# airwatch.net
KiCad netlist of a schematic drawn in EAGLE
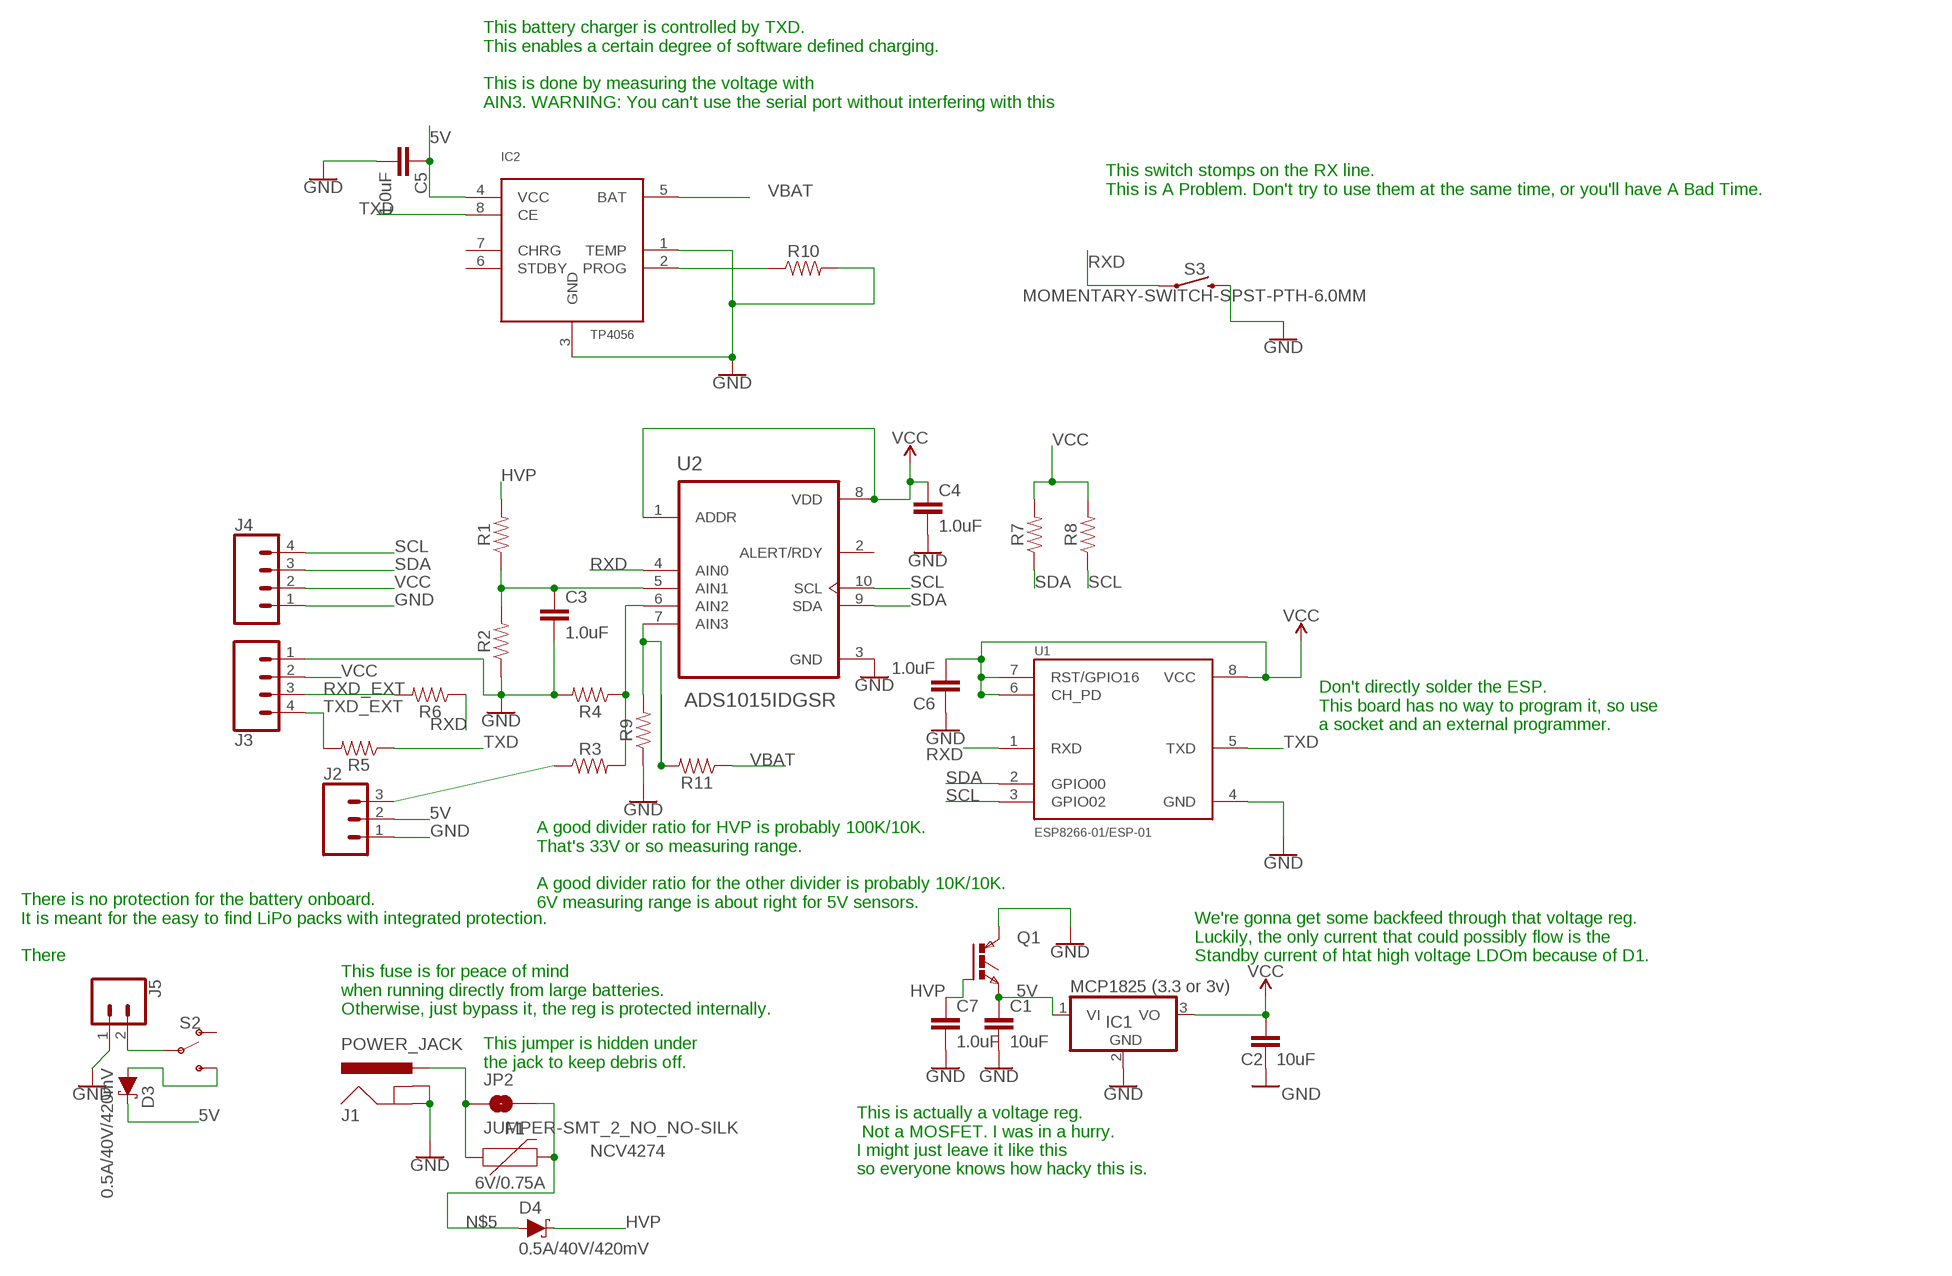
[diagram p0: schematic, sheet 1]

(export (version "E")
  (design (tool "Eeschema 10.0.6"))
  (components
    (comp (ref "C1")
      (value "10uF")
      (footprint "eagle-import:0805")
      (libsource (lib "eagle-import") (part "10UF-0805-10V-10%"))
    )
    (comp (ref "C2")
      (value "10uF")
      (footprint "eagle-import:0805")
      (libsource (lib "eagle-import") (part "10UF-0805-10V-10%"))
    )
    (comp (ref "C3")
      (value "1.0uF")
      (footprint "eagle-import:0805-EZ")
      (libsource (lib "eagle-import") (part "1.0UF-0805-25V-10%"))
    )
    (comp (ref "C4")
      (value "1.0uF")
      (footprint "eagle-import:0805-EZ")
      (libsource (lib "eagle-import") (part "1.0UF-0805-25V-10%"))
    )
    (comp (ref "C5")
      (value "1.0uF")
      (footprint "eagle-import:0805-EZ")
      (libsource (lib "eagle-import") (part "1.0UF-0805-25V-10%"))
    )
    (comp (ref "C6")
      (value "1.0uF")
      (footprint "eagle-import:1206-EZ")
      (libsource (lib "eagle-import") (part "1.0UF-1206-50V-10%"))
    )
    (comp (ref "C7")
      (value "1.0uF")
      (footprint "eagle-import:0805-EZ")
      (libsource (lib "eagle-import") (part "1.0UF-0805-25V-10%"))
    )
    (comp (ref "D3")
      (value "0.5A/40V/420mV")
      (footprint "eagle-import:SOD-323")
      (libsource (lib "eagle-import") (part "DIODE-SCHOTTKY-PMEG4005EJ"))
    )
    (comp (ref "D4")
      (value "0.5A/40V/420mV")
      (footprint "eagle-import:SOD-323")
      (libsource (lib "eagle-import") (part "DIODE-SCHOTTKY-PMEG4005EJ"))
    )
    (comp (ref "F1")
      (value "6V/0.75A")
      (footprint "eagle-import:1206")
      (libsource (lib "eagle-import") (part "PPTC_THREE-QUARTER-AMP"))
    )
    (comp (ref "IC1")
      (value "MCP1825 (3.3 or 3v)")
      (footprint "eagle-import:SOT223")
      (libsource (lib "eagle-import") (part "MCP1703DB"))
    )
    (comp (ref "IC2")
      (value "TP4056")
      (footprint "eagle-import:SOP-8")
      (fields (field (name "MF") "NanJing Top Power ASIC Corp.") (field (name "MP") "TP4056 "))
      (libsource (lib "eagle-import") (part "TP4056"))
    )
    (comp (ref "J1")
      (value "POWER_JACK")
      (footprint "eagle-import:POWER_JACK_PTH")
      (libsource (lib "eagle-import") (part "POWER_JACK"))
    )
    (comp (ref "J2")
      (value "CONN_03JST-PTH-VERT")
      (footprint "eagle-import:JST-3-PTH-VERT")
      (libsource (lib "eagle-import") (part "CONN_03JST-PTH-VERT"))
    )
    (comp (ref "J3")
      (value "CONN_04JST-PTH-VERT")
      (footprint "eagle-import:JST-4-PTH-VERT")
      (libsource (lib "eagle-import") (part "CONN_04JST-PTH-VERT"))
    )
    (comp (ref "J4")
      (value "CONN_04JST-PTH-VERT")
      (footprint "eagle-import:JST-4-PTH-VERT")
      (libsource (lib "eagle-import") (part "CONN_04JST-PTH-VERT"))
    )
    (comp (ref "J5")
      (value "CONN_02JST-PTH-2")
      (footprint "eagle-import:JST-2-PTH")
      (libsource (lib "eagle-import") (part "CONN_02JST-PTH-2"))
    )
    (comp (ref "JP2")
      (value "JUMPER-SMT_2_NO_NO-SILK")
      (footprint "eagle-import:SMT-JUMPER_2_NO_NO-SILK")
      (libsource (lib "eagle-import") (part "JUMPER-SMT_2_NO_NO-SILK"))
    )
    (comp (ref "Q1")
      (value "NCV4274")
      (footprint "eagle-import:TO252_STM")
      (libsource (lib "eagle-import") (part "IGBTTO252_STM"))
    )
    (comp (ref "R1")
      (value "RESISTOR0805")
      (footprint "eagle-import:0805-EZ")
      (libsource (lib "eagle-import") (part "RESISTOR0805"))
    )
    (comp (ref "R2")
      (value "RESISTOR0805")
      (footprint "eagle-import:0805-EZ")
      (libsource (lib "eagle-import") (part "RESISTOR0805"))
    )
    (comp (ref "R3")
      (value "RESISTOR0805")
      (footprint "eagle-import:0805-EZ")
      (libsource (lib "eagle-import") (part "RESISTOR0805"))
    )
    (comp (ref "R4")
      (value "RESISTOR0805")
      (footprint "eagle-import:0805-EZ")
      (libsource (lib "eagle-import") (part "RESISTOR0805"))
    )
    (comp (ref "R5")
      (value "RESISTOR0805")
      (footprint "eagle-import:0805-EZ")
      (libsource (lib "eagle-import") (part "RESISTOR0805"))
    )
    (comp (ref "R6")
      (value "RESISTOR0805")
      (footprint "eagle-import:0805-EZ")
      (libsource (lib "eagle-import") (part "RESISTOR0805"))
    )
    (comp (ref "R7")
      (value "RESISTOR0805")
      (footprint "eagle-import:0805-EZ")
      (libsource (lib "eagle-import") (part "RESISTOR0805"))
    )
    (comp (ref "R8")
      (value "RESISTOR0805")
      (footprint "eagle-import:0805-EZ")
      (libsource (lib "eagle-import") (part "RESISTOR0805"))
    )
    (comp (ref "R9")
      (value "RESISTOR0805")
      (footprint "eagle-import:0805-EZ")
      (libsource (lib "eagle-import") (part "RESISTOR0805"))
    )
    (comp (ref "R10")
      (value "RESISTOR0805")
      (footprint "eagle-import:0805-EZ")
      (libsource (lib "eagle-import") (part "RESISTOR0805"))
    )
    (comp (ref "R11")
      (value "RESISTOR0805")
      (footprint "eagle-import:0805-EZ")
      (libsource (lib "eagle-import") (part "RESISTOR0805"))
    )
    (comp (ref "S2")
      (value "SWITCH-SPDT-PTH-11.6X4.0MM-LOCK")
      (footprint "eagle-import:SWITCH_SPDT_PTH_11.6X4.0MM_LOCK")
      (libsource (lib "eagle-import") (part "SWITCH-SPDT-PTH-11.6X4.0MM-LOCK"))
    )
    (comp (ref "S3")
      (value "MOMENTARY-SWITCH-SPST-PTH-6.0MM")
      (footprint "eagle-import:TACTILE_SWITCH_PTH_6.0MM")
      (libsource (lib "eagle-import") (part "MOMENTARY-SWITCH-SPST-PTH-6.0MM"))
    )
    (comp (ref "U1")
      (value "ESP8266-01/ESP-01")
      (footprint "eagle-import:XCVR_ESP8266-01_ESP-01")
      (fields (field (name "MF") "AI-Thinker"))
      (libsource (lib "eagle-import") (part "ESP8266-01/ESP-01"))
    )
    (comp (ref "U2")
      (value "ADS1015IDGSR")
      (footprint "eagle-import:SOP50P490X110-10N")
      (fields (field (name "MF") "Texas Instruments"))
      (libsource (lib "eagle-import") (part "ADS1015IDGSR"))
    )
  )
  (nets
    (net (code "1") (name "/5V") (class "Default")
      (node (ref "C1") (pin "1") (pinfunction "1_1") (pintype "passive"))
      (node (ref "C5") (pin "1") (pinfunction "1_1") (pintype "passive"))
      (node (ref "D3") (pin "C") (pinfunction "C_C") (pintype "passive"))
      (node (ref "IC1") (pin "1") (pinfunction "VI_1") (pintype "input"))
      (node (ref "IC2") (pin "4") (pinfunction "VCC_4") (pintype "bidirectional"))
      (node (ref "J2") (pin "2") (pinfunction "2_2") (pintype "passive"))
      (node (ref "Q1") (pin "3") (pinfunction "E_3") (pintype "passive"))
    )
    (net (code "2") (name "/HVP") (class "Default")
      (node (ref "C7") (pin "1") (pinfunction "1_1") (pintype "passive"))
      (node (ref "D4") (pin "C") (pinfunction "C_C") (pintype "passive"))
      (node (ref "Q1") (pin "1") (pinfunction "G_1") (pintype "passive"))
      (node (ref "R1") (pin "2") (pinfunction "2_2") (pintype "passive"))
    )
    (net (code "3") (name "/N$5") (class "Default")
      (node (ref "D4") (pin "A") (pinfunction "A_A") (pintype "passive"))
      (node (ref "F1") (pin "2") (pinfunction "2_2") (pintype "bidirectional"))
      (node (ref "JP2") (pin "2") (pinfunction "2_2") (pintype "passive"))
    )
    (net (code "4") (name "/RXD") (class "Default")
      (node (ref "R6") (pin "1") (pinfunction "1_1") (pintype "passive"))
      (node (ref "S3") (pin "1") (pinfunction "1_1") (pintype "passive"))
      (node (ref "U1") (pin "1") (pinfunction "RXD_1") (pintype "input"))
      (node (ref "U2") (pin "4") (pinfunction "AIN0_4") (pintype "input"))
    )
    (net (code "5") (name "/RXD_EXT") (class "Default")
      (node (ref "J3") (pin "3") (pinfunction "3_3") (pintype "passive"))
      (node (ref "R6") (pin "2") (pinfunction "2_2") (pintype "passive"))
    )
    (net (code "6") (name "/SCL") (class "Default")
      (node (ref "J4") (pin "4") (pinfunction "4_4") (pintype "passive"))
      (node (ref "R8") (pin "1") (pinfunction "1_1") (pintype "passive"))
      (node (ref "U1") (pin "3") (pinfunction "GPIO02_3") (pintype "bidirectional"))
      (node (ref "U2") (pin "10") (pinfunction "SCL_10") (pintype "input"))
    )
    (net (code "7") (name "/SDA") (class "Default")
      (node (ref "J4") (pin "3") (pinfunction "3_3") (pintype "passive"))
      (node (ref "R7") (pin "1") (pinfunction "1_1") (pintype "passive"))
      (node (ref "U1") (pin "2") (pinfunction "GPIO00_2") (pintype "bidirectional"))
      (node (ref "U2") (pin "9") (pinfunction "SDA_9") (pintype "bidirectional"))
    )
    (net (code "8") (name "/TXD") (class "Default")
      (node (ref "IC2") (pin "8") (pinfunction "CE_8") (pintype "bidirectional"))
      (node (ref "R5") (pin "1") (pinfunction "1_1") (pintype "passive"))
      (node (ref "U1") (pin "5") (pinfunction "TXD_5") (pintype "output"))
    )
    (net (code "9") (name "/TXD_EXT") (class "Default")
      (node (ref "J3") (pin "4") (pinfunction "4_4") (pintype "passive"))
      (node (ref "R5") (pin "2") (pinfunction "2_2") (pintype "passive"))
    )
    (net (code "10") (name "/VBAT") (class "Default")
      (node (ref "D3") (pin "A") (pinfunction "A_A") (pintype "passive"))
      (node (ref "IC2") (pin "5") (pinfunction "BAT_5") (pintype "bidirectional"))
      (node (ref "R11") (pin "1") (pinfunction "1_1") (pintype "passive"))
      (node (ref "S2") (pin "3") (pinfunction "S_3") (pintype "passive"))
    )
    (net (code "11") (name "GND") (class "Default")
      (node (ref "C1") (pin "2") (pinfunction "2_2") (pintype "passive"))
      (node (ref "C2") (pin "2") (pinfunction "2_2") (pintype "passive"))
      (node (ref "C3") (pin "2") (pinfunction "2_2") (pintype "passive"))
      (node (ref "C4") (pin "2") (pinfunction "2_2") (pintype "passive"))
      (node (ref "C5") (pin "2") (pinfunction "2_2") (pintype "passive"))
      (node (ref "C6") (pin "1") (pinfunction "1_1") (pintype "passive"))
      (node (ref "C7") (pin "2") (pinfunction "2_2") (pintype "passive"))
      (node (ref "IC1") (pin "2") (pinfunction "GND_2") (pintype "passive"))
      (node (ref "IC2") (pin "1") (pinfunction "TEMP_1") (pintype "bidirectional"))
      (node (ref "IC2") (pin "3") (pinfunction "GND_3") (pintype "bidirectional"))
      (node (ref "J1") (pin "GND") (pinfunction "GND_GND") (pintype "bidirectional"))
      (node (ref "J1") (pin "GNDBREAK") (pinfunction "GNDBREAK_GNDBREAK") (pintype "bidirectional"))
      (node (ref "J2") (pin "1") (pinfunction "1_1") (pintype "passive"))
      (node (ref "J3") (pin "1") (pinfunction "1_1") (pintype "passive"))
      (node (ref "J4") (pin "1") (pinfunction "1_1") (pintype "passive"))
      (node (ref "J5") (pin "1") (pinfunction "1_1") (pintype "passive"))
      (node (ref "Q1") (pin "2") (pinfunction "C_2") (pintype "passive"))
      (node (ref "R10") (pin "2") (pinfunction "2_2") (pintype "passive"))
      (node (ref "R2") (pin "1") (pinfunction "1_1") (pintype "passive"))
      (node (ref "R4") (pin "2") (pinfunction "2_2") (pintype "passive"))
      (node (ref "R9") (pin "1") (pinfunction "1_1") (pintype "passive"))
      (node (ref "S3") (pin "3") (pinfunction "2_3") (pintype "passive"))
      (node (ref "U1") (pin "4") (pinfunction "GND_4") (pintype "power_in"))
      (node (ref "U2") (pin "3") (pinfunction "GND_3") (pintype "power_in"))
    )
    (net (code "12") (name "Net-(F1-Pad1)") (class "Default")
      (node (ref "F1") (pin "1") (pinfunction "1_1") (pintype "bidirectional"))
      (node (ref "J1") (pin "PWR") (pinfunction "PWR_PWR") (pintype "bidirectional"))
      (node (ref "JP2") (pin "1") (pinfunction "1_1") (pintype "passive"))
    )
    (net (code "13") (name "Net-(IC2-PROG)") (class "Default")
      (node (ref "IC2") (pin "2") (pinfunction "PROG_2") (pintype "bidirectional"))
      (node (ref "R10") (pin "1") (pinfunction "1_1") (pintype "passive"))
    )
    (net (code "14") (name "Net-(J2-Pad3)") (class "Default")
      (node (ref "J2") (pin "3") (pinfunction "3_3") (pintype "passive"))
      (node (ref "R3") (pin "1") (pinfunction "1_1") (pintype "passive"))
    )
    (net (code "15") (name "Net-(S2-P)") (class "Default")
      (node (ref "J5") (pin "2") (pinfunction "2_2") (pintype "passive"))
      (node (ref "S2") (pin "2") (pinfunction "P_2") (pintype "passive"))
    )
    (net (code "16") (name "Net-(U2-AIN1)") (class "Default")
      (node (ref "C3") (pin "1") (pinfunction "1_1") (pintype "passive"))
      (node (ref "R1") (pin "1") (pinfunction "1_1") (pintype "passive"))
      (node (ref "R2") (pin "2") (pinfunction "2_2") (pintype "passive"))
      (node (ref "U2") (pin "5") (pinfunction "AIN1_5") (pintype "input"))
    )
    (net (code "17") (name "Net-(U2-AIN2)") (class "Default")
      (node (ref "R3") (pin "2") (pinfunction "2_2") (pintype "passive"))
      (node (ref "R4") (pin "1") (pinfunction "1_1") (pintype "passive"))
      (node (ref "U2") (pin "6") (pinfunction "AIN2_6") (pintype "input"))
    )
    (net (code "18") (name "Net-(U2-AIN3)") (class "Default")
      (node (ref "R11") (pin "2") (pinfunction "2_2") (pintype "passive"))
      (node (ref "R9") (pin "2") (pinfunction "2_2") (pintype "passive"))
      (node (ref "U2") (pin "7") (pinfunction "AIN3_7") (pintype "input"))
    )
    (net (code "19") (name "VCC") (class "Default")
      (node (ref "C2") (pin "1") (pinfunction "1_1") (pintype "passive"))
      (node (ref "C4") (pin "1") (pinfunction "1_1") (pintype "passive"))
      (node (ref "C6") (pin "2") (pinfunction "2_2") (pintype "passive"))
      (node (ref "IC1") (pin "3") (pinfunction "VO_3") (pintype "passive"))
      (node (ref "J3") (pin "2") (pinfunction "2_2") (pintype "passive"))
      (node (ref "J4") (pin "2") (pinfunction "2_2") (pintype "passive"))
      (node (ref "R7") (pin "2") (pinfunction "2_2") (pintype "passive"))
      (node (ref "R8") (pin "2") (pinfunction "2_2") (pintype "passive"))
      (node (ref "U1") (pin "6") (pinfunction "CH_PD_6") (pintype "input"))
      (node (ref "U1") (pin "7") (pinfunction "RST/GPIO16_7") (pintype "input"))
      (node (ref "U1") (pin "8") (pinfunction "VCC_8") (pintype "power_in"))
      (node (ref "U2") (pin "1") (pinfunction "ADDR_1") (pintype "input"))
      (node (ref "U2") (pin "8") (pinfunction "VDD_8") (pintype "power_in"))
    )
    (net (code "20") (name "unconnected-(IC2-CHRG-Pad7)") (class "Default")
      (node (ref "IC2") (pin "7") (pinfunction "CHRG_7") (pintype "bidirectional"))
    )
    (net (code "21") (name "unconnected-(IC2-STDBY-Pad6)") (class "Default")
      (node (ref "IC2") (pin "6") (pinfunction "STDBY_6") (pintype "bidirectional"))
    )
    (net (code "22") (name "unconnected-(S2-O-Pad1)") (class "Default")
      (node (ref "S2") (pin "1") (pinfunction "O_1") (pintype "passive"))
    )
    (net (code "23") (name "unconnected-(U2-ALERT{slash}RDY-Pad2)") (class "Default")
      (node (ref "U2") (pin "2") (pinfunction "ALERT/RDY_2") (pintype "output"))
    )
  )
)
